# AD603_PGA.net
KiCad netlist of a schematic drawn in Altium Designer
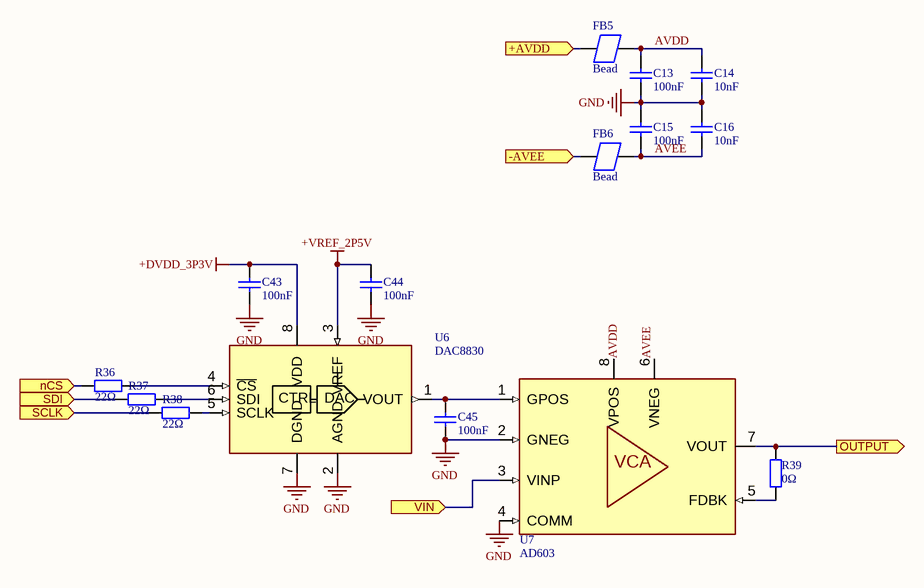
[diagram p0: AD603_PGA.SchDoc]

(export (version "E")
  (design (tool "Eeschema 10.0.6"))
  (components
    (comp (ref "C13")
      (value "100nF")
      (footprint "0603_C")
      (description "贴片电容")
      (libsource (lib "Miscellaneous Devices LC") (part "0603 100nF (104) 10% 50V"))
    )
    (comp (ref "C14")
      (value "10nF")
      (footprint "0603_C")
      (description "贴片电容")
      (libsource (lib "Miscellaneous Devices LC") (part "0603 10nF (103) 10% 50V"))
    )
    (comp (ref "C15")
      (value "100nF")
      (footprint "0603_C")
      (description "贴片电容")
      (libsource (lib "Miscellaneous Devices LC") (part "0603 100nF (104) 10% 50V"))
    )
    (comp (ref "C16")
      (value "10nF")
      (footprint "0603_C")
      (description "贴片电容")
      (libsource (lib "Miscellaneous Devices LC") (part "0603 10nF (103) 10% 50V"))
    )
    (comp (ref "C43")
      (value "100nF")
      (footprint "0603_C")
      (description "贴片电容")
      (libsource (lib "Miscellaneous Devices LC") (part "0603 100nF (104) 10% 50V"))
    )
    (comp (ref "C44")
      (value "100nF")
      (footprint "0603_C")
      (description "贴片电容")
      (libsource (lib "Miscellaneous Devices LC") (part "0603 100nF (104) 10% 50V"))
    )
    (comp (ref "C45")
      (value "100nF")
      (footprint "0603_C")
      (description "贴片电容")
      (libsource (lib "Miscellaneous Devices LC") (part "0603 100nF (104) 10% 50V"))
    )
    (comp (ref "FB5") (value "Bead") (footprint "0805_L") (libsource (lib "OlvkLib") (part "Bead")))
    (comp (ref "FB6") (value "Bead") (footprint "0805_L") (libsource (lib "OlvkLib") (part "Bead")))
    (comp (ref "R36")
      (value "22Ω")
      (footprint "0603_R")
      (description "贴片电阻")
      (libsource (lib "Miscellaneous Devices LC") (part "0603 22Ω (22R0) 1%"))
    )
    (comp (ref "R37")
      (value "22Ω")
      (footprint "0603_R")
      (description "贴片电阻")
      (libsource (lib "Miscellaneous Devices LC") (part "0603 22Ω (22R0) 1%"))
    )
    (comp (ref "R38")
      (value "22Ω")
      (footprint "0603_R")
      (description "贴片电阻")
      (libsource (lib "Miscellaneous Devices LC") (part "0603 22Ω (22R0) 1%"))
    )
    (comp (ref "R39")
      (value "0Ω")
      (footprint "0603_R")
      (description "贴片电阻")
      (libsource (lib "Miscellaneous Devices LC") (part "0603 0Ω (0R0) 1%"))
    )
    (comp (ref "U6")
      (value "DAC8830")
      (footprint "SOIC127P600X175-8M")
      (libsource (lib "OlvkLib") (part "DAC8830"))
    )
    (comp (ref "U7")
      (value "AD603")
      (footprint "SOIC127P600X175-8M")
      (libsource (lib "OlvkLib") (part "AD603"))
    )
  )
  (nets
    (net (code "1") (name "+DVDD_3P3V") (class "Default")
      (node (ref "C43") (pin "2") (pinfunction "2_2") (pintype "passive"))
      (node (ref "U6") (pin "8") (pinfunction "VDD_8") (pintype "power_in"))
    )
    (net (code "2") (name "+VREF_2P5V") (class "Default")
      (node (ref "C44") (pin "2") (pinfunction "2_2") (pintype "passive"))
      (node (ref "U6") (pin "3") (pinfunction "VREF_3") (pintype "input"))
    )
    (net (code "3") (name "/+AVDD") (class "Default")
      (node (ref "FB5") (pin "1") (pinfunction "1_1") (pintype "passive"))
    )
    (net (code "4") (name "/-AVEE") (class "Default")
      (node (ref "FB6") (pin "1") (pinfunction "1_1") (pintype "passive"))
    )
    (net (code "5") (name "/AVDD") (class "Default")
      (node (ref "C13") (pin "2") (pinfunction "2_2") (pintype "passive"))
      (node (ref "C14") (pin "2") (pinfunction "2_2") (pintype "passive"))
      (node (ref "FB5") (pin "2") (pinfunction "2_2") (pintype "passive"))
    )
    (net (code "6") (name "/AVEE") (class "Default")
      (node (ref "C15") (pin "2") (pinfunction "2_2") (pintype "passive"))
      (node (ref "C16") (pin "2") (pinfunction "2_2") (pintype "passive"))
      (node (ref "FB6") (pin "2") (pinfunction "2_2") (pintype "passive"))
      (node (ref "U7") (pin "6") (pinfunction "VNEG_6") (pintype "power_in"))
    )
    (net (code "7") (name "/OUTPUT") (class "Default")
      (node (ref "R39") (pin "2") (pinfunction "2_2") (pintype "passive"))
      (node (ref "U7") (pin "7") (pinfunction "VOUT_7") (pintype "open_collector"))
    )
    (net (code "8") (name "/SCLK") (class "Default")
      (node (ref "R38") (pin "1") (pinfunction "1_1") (pintype "passive"))
    )
    (net (code "9") (name "/SDI") (class "Default")
      (node (ref "R37") (pin "1") (pinfunction "1_1") (pintype "passive"))
    )
    (net (code "10") (name "/VIN") (class "Default")
      (node (ref "U7") (pin "3") (pinfunction "VINP_3") (pintype "input"))
    )
    (net (code "11") (name "/nCS") (class "Default")
      (node (ref "R36") (pin "1") (pinfunction "1_1") (pintype "passive"))
    )
    (net (code "12") (name "GND") (class "Default")
      (node (ref "C13") (pin "1") (pinfunction "1_1") (pintype "passive"))
      (node (ref "C14") (pin "1") (pinfunction "1_1") (pintype "passive"))
      (node (ref "C15") (pin "1") (pinfunction "1_1") (pintype "passive"))
      (node (ref "C16") (pin "1") (pinfunction "1_1") (pintype "passive"))
      (node (ref "C43") (pin "1") (pinfunction "1_1") (pintype "passive"))
      (node (ref "C44") (pin "1") (pinfunction "1_1") (pintype "passive"))
      (node (ref "C45") (pin "1") (pinfunction "1_1") (pintype "passive"))
      (node (ref "U6") (pin "2") (pinfunction "AGND_2") (pintype "power_in"))
      (node (ref "U6") (pin "7") (pinfunction "DGND_7") (pintype "power_in"))
      (node (ref "U7") (pin "2") (pinfunction "GNEG_2") (pintype "input"))
      (node (ref "U7") (pin "4") (pinfunction "COMM_4") (pintype "input"))
    )
    (net (code "13") (name "Net-(U6-SCLK)") (class "Default")
      (node (ref "R38") (pin "2") (pinfunction "2_2") (pintype "passive"))
      (node (ref "U6") (pin "5") (pinfunction "SCLK_5") (pintype "input"))
    )
    (net (code "14") (name "Net-(U6-SDI)") (class "Default")
      (node (ref "R37") (pin "2") (pinfunction "2_2") (pintype "passive"))
      (node (ref "U6") (pin "6") (pinfunction "SDI_6") (pintype "input"))
    )
    (net (code "15") (name "Net-(U6-VOUT)") (class "Default")
      (node (ref "C45") (pin "2") (pinfunction "2_2") (pintype "passive"))
      (node (ref "U6") (pin "1") (pinfunction "VOUT_1") (pintype "output"))
      (node (ref "U7") (pin "1") (pinfunction "GPOS_1") (pintype "input"))
    )
    (net (code "16") (name "Net-(U6-~{CS})") (class "Default")
      (node (ref "R36") (pin "2") (pinfunction "2_2") (pintype "passive"))
      (node (ref "U6") (pin "4") (pinfunction "~{CS}_4") (pintype "input"))
    )
    (net (code "17") (name "Net-(U7-FDBK)") (class "Default")
      (node (ref "R39") (pin "1") (pinfunction "1_1") (pintype "passive"))
      (node (ref "U7") (pin "5") (pinfunction "FDBK_5") (pintype "input"))
    )
    (net (code "18") (name "unconnected-(U7-VPOS-Pad8)") (class "Default")
      (node (ref "U7") (pin "8") (pinfunction "VPOS_8") (pintype "power_in"))
    )
  )
)
